# Pomodoro.net
KiCad netlist of a schematic drawn in EAGLE
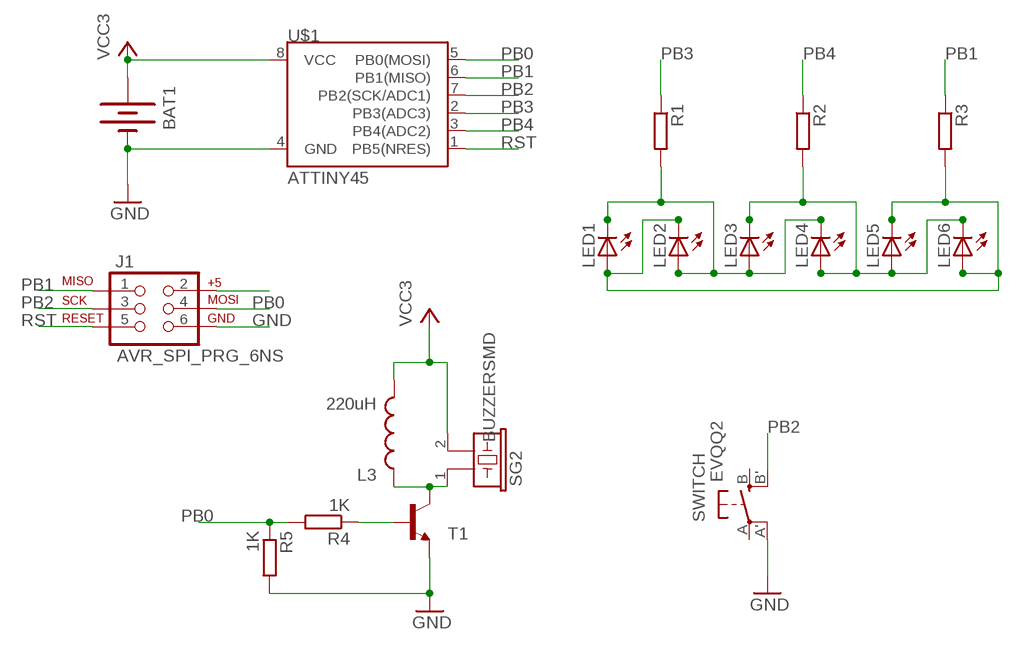
[diagram p0: schematic, sheet 1]

(export (version "E")
  (design (tool "Eeschema 10.0.6"))
  (components
    (comp (ref "BAT1")
      (value "BATTERY20SMD")
      (footprint "eagle-import:BATTCON_20MM")
      (libsource (lib "eagle-import") (part "BATTERY20SMD"))
    )
    (comp (ref "J1")
      (value "AVR_SPI_PRG_6NS")
      (footprint "eagle-import:2X3-NS")
      (libsource (lib "eagle-import") (part "AVR_SPI_PRG_6NS"))
    )
    (comp (ref "L3")
      (value "220uH")
      (footprint "eagle-import:1007")
      (libsource (lib "eagle-import") (part "INDUCTOR1007"))
    )
    (comp (ref "LED1")
      (value "LEDCHIPLED_0805")
      (footprint "eagle-import:CHIPLED_0805")
      (libsource (lib "eagle-import") (part "LEDCHIPLED_0805"))
    )
    (comp (ref "LED2")
      (value "LEDCHIPLED_0805")
      (footprint "eagle-import:CHIPLED_0805")
      (libsource (lib "eagle-import") (part "LEDCHIPLED_0805"))
    )
    (comp (ref "LED3")
      (value "LEDCHIPLED_0805")
      (footprint "eagle-import:CHIPLED_0805")
      (libsource (lib "eagle-import") (part "LEDCHIPLED_0805"))
    )
    (comp (ref "LED4")
      (value "LEDCHIPLED_0805")
      (footprint "eagle-import:CHIPLED_0805")
      (libsource (lib "eagle-import") (part "LEDCHIPLED_0805"))
    )
    (comp (ref "LED5")
      (value "LEDCHIPLED_0805")
      (footprint "eagle-import:CHIPLED_0805")
      (libsource (lib "eagle-import") (part "LEDCHIPLED_0805"))
    )
    (comp (ref "LED6")
      (value "LEDCHIPLED_0805")
      (footprint "eagle-import:CHIPLED_0805")
      (libsource (lib "eagle-import") (part "LEDCHIPLED_0805"))
    )
    (comp (ref "R1")
      (value "R-EU_R0805")
      (footprint "eagle-import:R0805")
      (libsource (lib "eagle-import") (part "R-EU_R0805"))
    )
    (comp (ref "R2")
      (value "R-EU_R0805")
      (footprint "eagle-import:R0805")
      (libsource (lib "eagle-import") (part "R-EU_R0805"))
    )
    (comp (ref "R3")
      (value "R-EU_R0805")
      (footprint "eagle-import:R0805")
      (libsource (lib "eagle-import") (part "R-EU_R0805"))
    )
    (comp (ref "R4")
      (value "1K")
      (footprint "eagle-import:R0805")
      (libsource (lib "eagle-import") (part "R-EU_R0805"))
    )
    (comp (ref "R5")
      (value "1K")
      (footprint "eagle-import:R0805")
      (libsource (lib "eagle-import") (part "R-EU_R0805"))
    )
    (comp (ref "SG2")
      (value "BUZZERSMD")
      (footprint "eagle-import:KOBITONE-254-PB501-ROX")
      (libsource (lib "eagle-import") (part "BUZZERSMD"))
    )
    (comp (ref "SWITCH")
      (value "EVQQ2")
      (footprint "eagle-import:EVQ-Q2")
      (libsource (lib "eagle-import") (part "EVQQ2"))
    )
    (comp (ref "T1")
      (value "BC849-NPN-SOT23-BEC")
      (footprint "eagle-import:SOT23-BEC")
      (libsource (lib "eagle-import") (part "-NPN-SOT23-BECBC849"))
    )
    (comp (ref "U$1")
      (value "ATTINY45")
      (footprint "eagle-import:SO08-EIAJ")
      (libsource (lib "eagle-import") (part "ATTINY45"))
    )
  )
  (nets
    (net (code "1") (name "/PB0") (class "Default")
      (node (ref "J1") (pin "4") (pinfunction "4_4") (pintype "passive"))
      (node (ref "R4") (pin "2") (pinfunction "2_2") (pintype "passive"))
      (node (ref "R5") (pin "1") (pinfunction "1_1") (pintype "passive"))
      (node (ref "U$1") (pin "5") (pinfunction "PB0(MOSI)_5") (pintype "bidirectional"))
    )
    (net (code "2") (name "/PB1") (class "Default")
      (node (ref "J1") (pin "1") (pinfunction "1_1") (pintype "passive"))
      (node (ref "R3") (pin "1") (pinfunction "1_1") (pintype "passive"))
      (node (ref "U$1") (pin "6") (pinfunction "PB1(MISO)_6") (pintype "bidirectional"))
    )
    (net (code "3") (name "/PB2") (class "Default")
      (node (ref "J1") (pin "3") (pinfunction "3_3") (pintype "passive"))
      (node (ref "SWITCH") (pin "B'") (pinfunction "S1_B'") (pintype "passive"))
      (node (ref "U$1") (pin "7") (pinfunction "PB2(SCK/ADC1)_7") (pintype "bidirectional"))
    )
    (net (code "4") (name "/PB3") (class "Default")
      (node (ref "R1") (pin "1") (pinfunction "1_1") (pintype "passive"))
      (node (ref "U$1") (pin "2") (pinfunction "PB3(ADC3)_2") (pintype "bidirectional"))
    )
    (net (code "5") (name "/PB4") (class "Default")
      (node (ref "R2") (pin "1") (pinfunction "1_1") (pintype "passive"))
      (node (ref "U$1") (pin "3") (pinfunction "PB4(ADC2)_3") (pintype "bidirectional"))
    )
    (net (code "6") (name "/RST") (class "Default")
      (node (ref "J1") (pin "5") (pinfunction "5_5") (pintype "passive"))
      (node (ref "U$1") (pin "1") (pinfunction "PB5(NRES)_1") (pintype "bidirectional"))
    )
    (net (code "7") (name "GND") (class "Default")
      (node (ref "BAT1") (pin "2") (pinfunction "-_2") (pintype "power_in"))
      (node (ref "J1") (pin "6") (pinfunction "6_6") (pintype "passive"))
      (node (ref "R5") (pin "2") (pinfunction "2_2") (pintype "passive"))
      (node (ref "SWITCH") (pin "A'") (pinfunction "P1_A'") (pintype "passive"))
      (node (ref "T1") (pin "E") (pinfunction "E_E") (pintype "passive"))
      (node (ref "U$1") (pin "4") (pinfunction "GND_4") (pintype "bidirectional"))
    )
    (net (code "8") (name "Net-(L3-Pad1)") (class "Default")
      (node (ref "L3") (pin "1") (pinfunction "1_1") (pintype "passive"))
      (node (ref "SG2") (pin "1") (pinfunction "1_1") (pintype "passive"))
      (node (ref "T1") (pin "C") (pinfunction "C_C") (pintype "passive"))
    )
    (net (code "9") (name "Net-(LED1-PadA)") (class "Default")
      (node (ref "LED1") (pin "A") (pinfunction "A_A") (pintype "passive"))
      (node (ref "LED2") (pin "C") (pinfunction "C_C") (pintype "passive"))
      (node (ref "LED5") (pin "C") (pinfunction "C_C") (pintype "passive"))
      (node (ref "LED6") (pin "A") (pinfunction "A_A") (pintype "passive"))
      (node (ref "R3") (pin "2") (pinfunction "2_2") (pintype "passive"))
    )
    (net (code "10") (name "Net-(LED1-PadC)") (class "Default")
      (node (ref "LED1") (pin "C") (pinfunction "C_C") (pintype "passive"))
      (node (ref "LED2") (pin "A") (pinfunction "A_A") (pintype "passive"))
      (node (ref "LED3") (pin "A") (pinfunction "A_A") (pintype "passive"))
      (node (ref "LED4") (pin "C") (pinfunction "C_C") (pintype "passive"))
      (node (ref "R1") (pin "2") (pinfunction "2_2") (pintype "passive"))
    )
    (net (code "11") (name "Net-(LED3-PadC)") (class "Default")
      (node (ref "LED3") (pin "C") (pinfunction "C_C") (pintype "passive"))
      (node (ref "LED4") (pin "A") (pinfunction "A_A") (pintype "passive"))
      (node (ref "LED5") (pin "A") (pinfunction "A_A") (pintype "passive"))
      (node (ref "LED6") (pin "C") (pinfunction "C_C") (pintype "passive"))
      (node (ref "R2") (pin "2") (pinfunction "2_2") (pintype "passive"))
    )
    (net (code "12") (name "Net-(R4-Pad1)") (class "Default")
      (node (ref "R4") (pin "1") (pinfunction "1_1") (pintype "passive"))
      (node (ref "T1") (pin "B") (pinfunction "B_B") (pintype "passive"))
    )
    (net (code "13") (name "VCC3") (class "Default")
      (node (ref "BAT1") (pin "1") (pinfunction "+_1") (pintype "power_in"))
      (node (ref "BAT1") (pin "3") (pinfunction "+_3") (pintype "power_in"))
      (node (ref "L3") (pin "2") (pinfunction "2_2") (pintype "passive"))
      (node (ref "SG2") (pin "2") (pinfunction "2_2") (pintype "passive"))
      (node (ref "U$1") (pin "8") (pinfunction "VCC_8") (pintype "bidirectional"))
    )
    (net (code "14") (name "unconnected-(J1-Pad2)") (class "Default")
      (node (ref "J1") (pin "2") (pinfunction "2_2") (pintype "passive"))
    )
    (net (code "15") (name "unconnected-(SWITCH-P-PadA)") (class "Default")
      (node (ref "SWITCH") (pin "A") (pinfunction "P_A") (pintype "passive"))
    )
    (net (code "16") (name "unconnected-(SWITCH-S-PadB)") (class "Default")
      (node (ref "SWITCH") (pin "B") (pinfunction "S_B") (pintype "passive"))
    )
  )
)
